# 16-PWR_2.net
KiCad netlist of a schematic drawn in Altium Designer
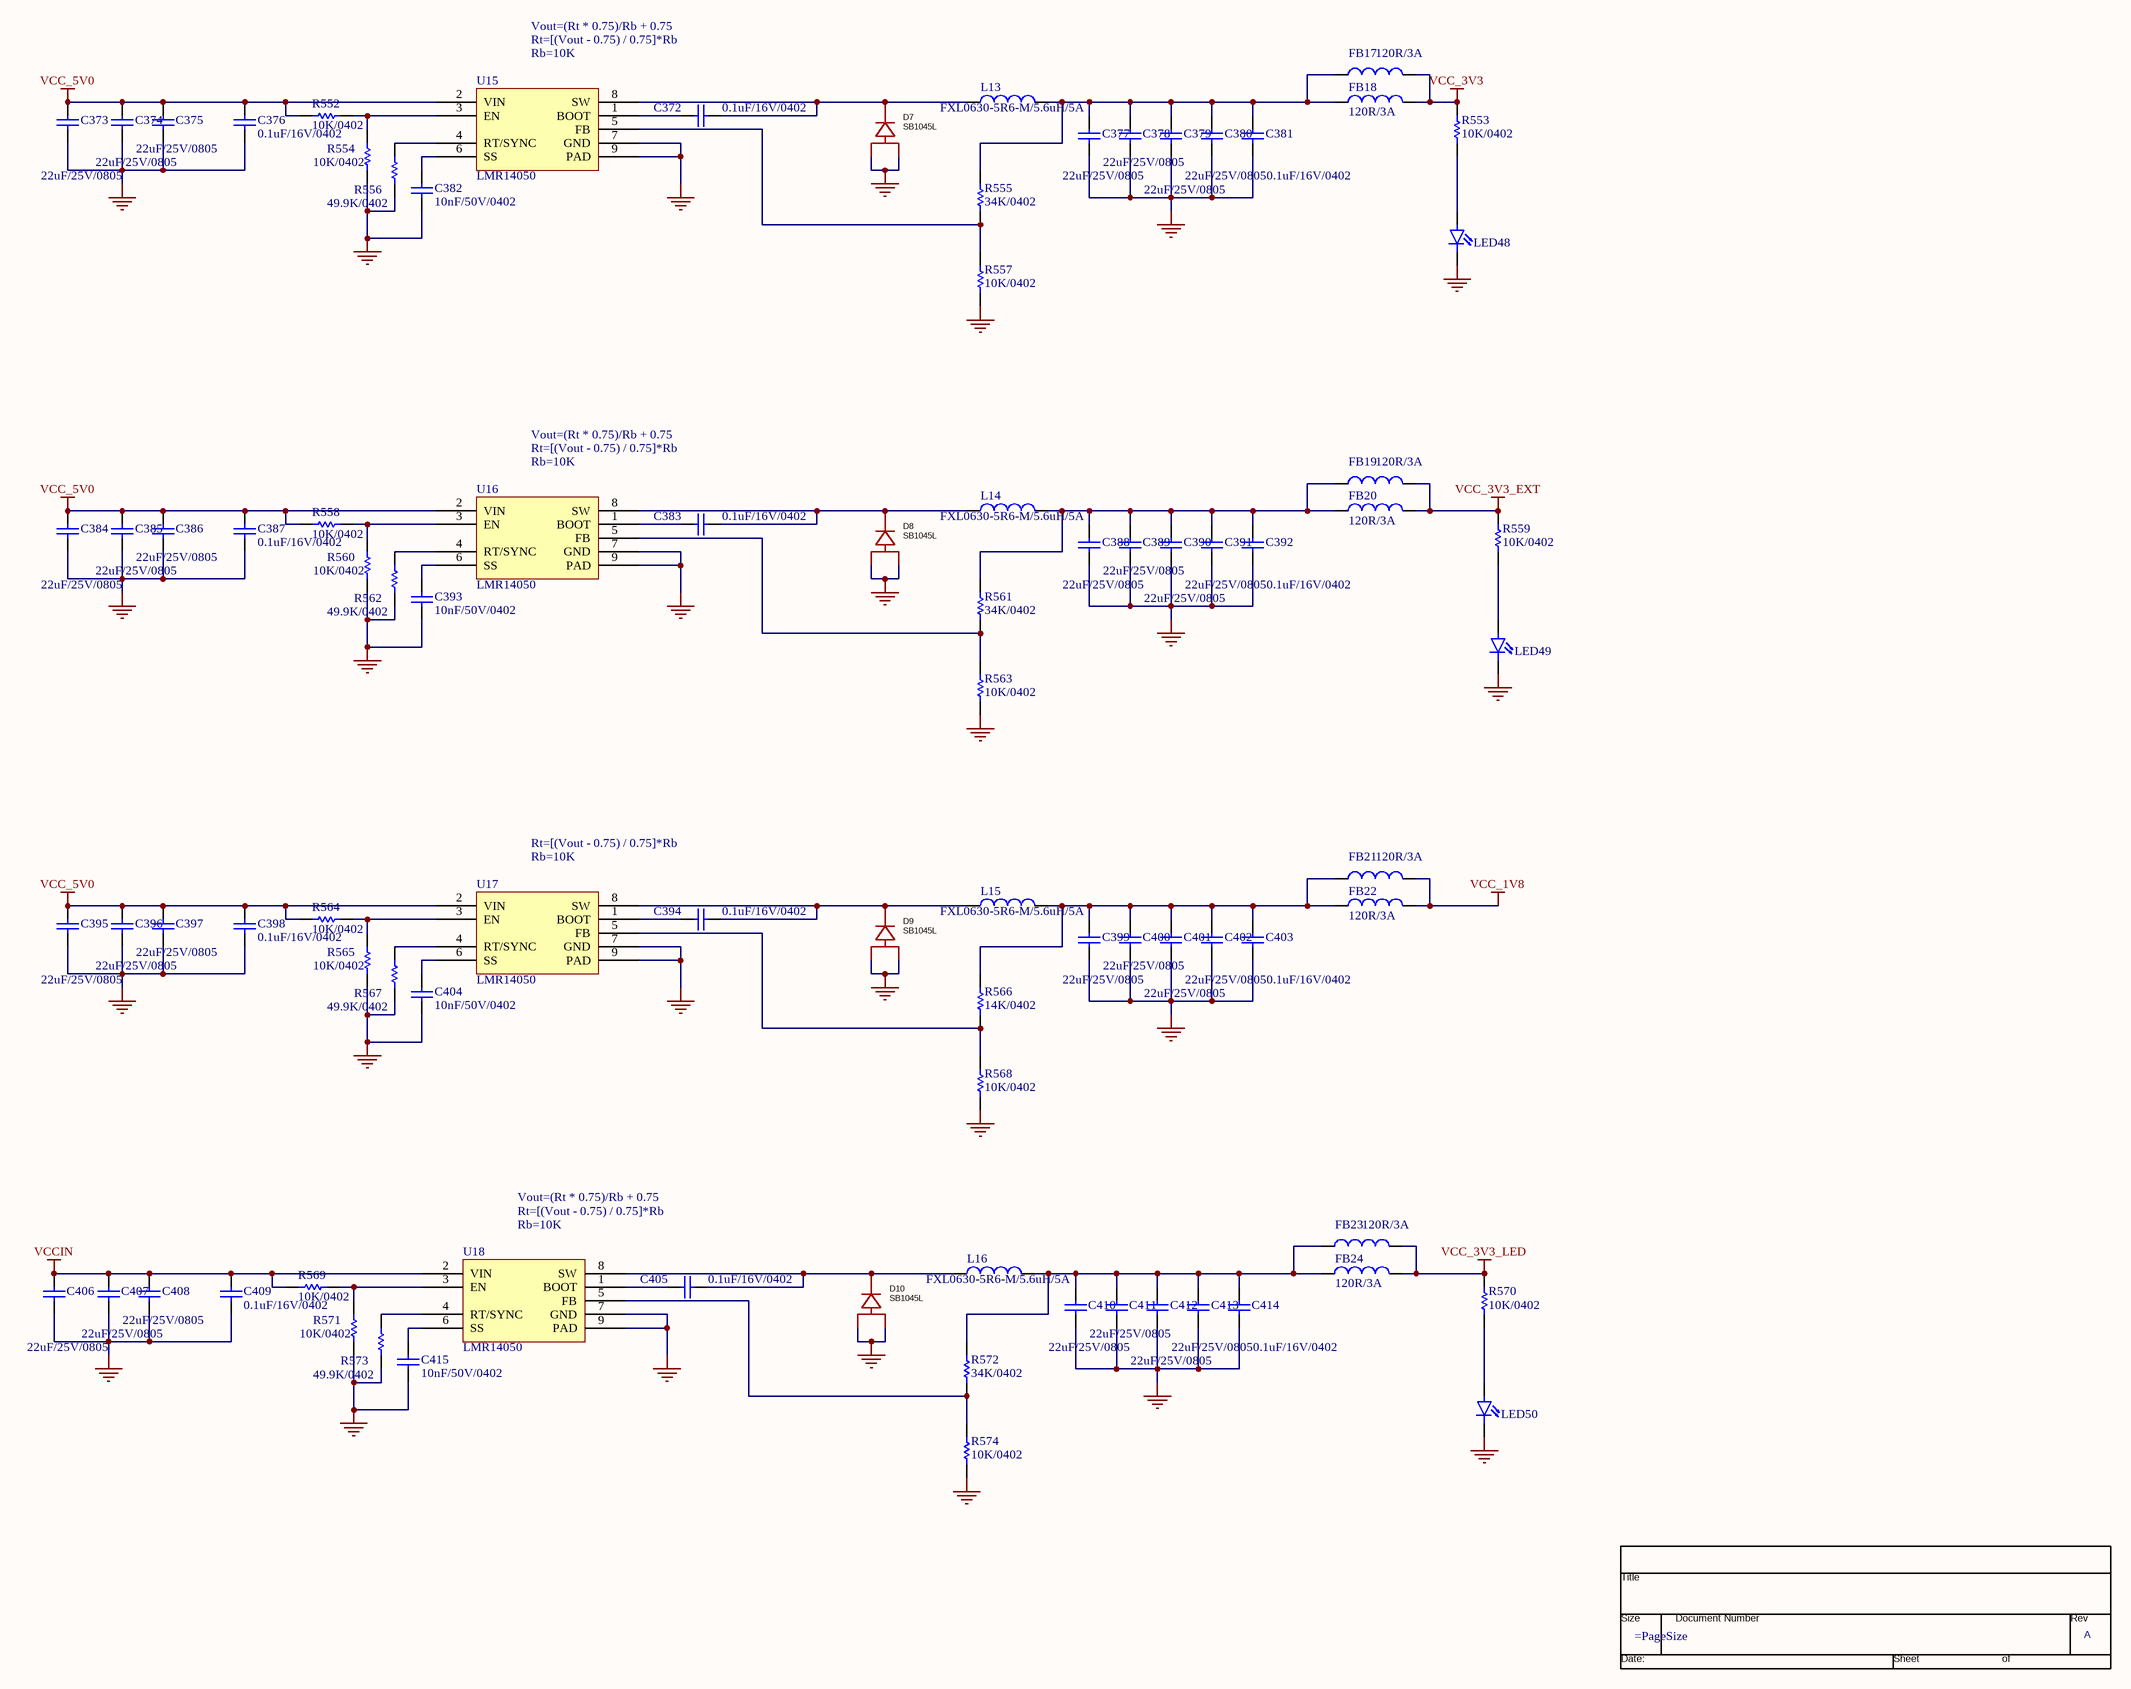
[diagram p0: 16-PWR_2.SchDoc]

(export (version "E")
  (design (tool "Eeschema 10.0.6"))
  (components
    (comp (ref "C372")
      (value "0.1uF/16V/0402")
      (description "Capacitor")
      (fields (field (name "PUBLISHER") "Altium Limited"))
      (libsource (lib "LIBS") (part "CAP"))
    )
    (comp (ref "C373")
      (value "22uF/25V/0805")
      (description "Capacitor")
      (fields (field (name "PUBLISHER") "Altium Limited"))
      (libsource (lib "LIBS") (part "CAP"))
    )
    (comp (ref "C374")
      (value "22uF/25V/0805")
      (description "Capacitor")
      (fields (field (name "PUBLISHER") "Altium Limited"))
      (libsource (lib "LIBS") (part "CAP"))
    )
    (comp (ref "C375")
      (value "22uF/25V/0805")
      (description "Capacitor")
      (fields (field (name "PUBLISHER") "Altium Limited"))
      (libsource (lib "LIBS") (part "CAP"))
    )
    (comp (ref "C376")
      (value "0.1uF/16V/0402")
      (description "Capacitor")
      (fields (field (name "PUBLISHER") "Altium Limited"))
      (libsource (lib "LIBS") (part "CAP"))
    )
    (comp (ref "C377")
      (value "22uF/25V/0805")
      (description "Capacitor")
      (fields (field (name "PUBLISHER") "Altium Limited"))
      (libsource (lib "LIBS") (part "CAP"))
    )
    (comp (ref "C378")
      (value "22uF/25V/0805")
      (description "Capacitor")
      (fields (field (name "PUBLISHER") "Altium Limited"))
      (libsource (lib "LIBS") (part "CAP"))
    )
    (comp (ref "C379")
      (value "22uF/25V/0805")
      (description "Capacitor")
      (fields (field (name "PUBLISHER") "Altium Limited"))
      (libsource (lib "LIBS") (part "CAP"))
    )
    (comp (ref "C380")
      (value "22uF/25V/0805")
      (description "Capacitor")
      (fields (field (name "PUBLISHER") "Altium Limited"))
      (libsource (lib "LIBS") (part "CAP"))
    )
    (comp (ref "C381")
      (value "0.1uF/16V/0402")
      (description "Capacitor")
      (fields (field (name "PUBLISHER") "Altium Limited"))
      (libsource (lib "LIBS") (part "CAP"))
    )
    (comp (ref "C382")
      (value "10nF/50V/0402")
      (description "Capacitor")
      (fields (field (name "PUBLISHER") "Altium Limited"))
      (libsource (lib "LIBS") (part "CAP"))
    )
    (comp (ref "C383")
      (value "0.1uF/16V/0402")
      (description "Capacitor")
      (fields (field (name "PUBLISHER") "Altium Limited"))
      (libsource (lib "LIBS") (part "CAP"))
    )
    (comp (ref "C384")
      (value "22uF/25V/0805")
      (description "Capacitor")
      (fields (field (name "PUBLISHER") "Altium Limited"))
      (libsource (lib "LIBS") (part "CAP"))
    )
    (comp (ref "C385")
      (value "22uF/25V/0805")
      (description "Capacitor")
      (fields (field (name "PUBLISHER") "Altium Limited"))
      (libsource (lib "LIBS") (part "CAP"))
    )
    (comp (ref "C386")
      (value "22uF/25V/0805")
      (description "Capacitor")
      (fields (field (name "PUBLISHER") "Altium Limited"))
      (libsource (lib "LIBS") (part "CAP"))
    )
    (comp (ref "C387")
      (value "0.1uF/16V/0402")
      (description "Capacitor")
      (fields (field (name "PUBLISHER") "Altium Limited"))
      (libsource (lib "LIBS") (part "CAP"))
    )
    (comp (ref "C388")
      (value "22uF/25V/0805")
      (description "Capacitor")
      (fields (field (name "PUBLISHER") "Altium Limited"))
      (libsource (lib "LIBS") (part "CAP"))
    )
    (comp (ref "C389")
      (value "22uF/25V/0805")
      (description "Capacitor")
      (fields (field (name "PUBLISHER") "Altium Limited"))
      (libsource (lib "LIBS") (part "CAP"))
    )
    (comp (ref "C390")
      (value "22uF/25V/0805")
      (description "Capacitor")
      (fields (field (name "PUBLISHER") "Altium Limited"))
      (libsource (lib "LIBS") (part "CAP"))
    )
    (comp (ref "C391")
      (value "22uF/25V/0805")
      (description "Capacitor")
      (fields (field (name "PUBLISHER") "Altium Limited"))
      (libsource (lib "LIBS") (part "CAP"))
    )
    (comp (ref "C392")
      (value "0.1uF/16V/0402")
      (description "Capacitor")
      (fields (field (name "PUBLISHER") "Altium Limited"))
      (libsource (lib "LIBS") (part "CAP"))
    )
    (comp (ref "C393")
      (value "10nF/50V/0402")
      (description "Capacitor")
      (fields (field (name "PUBLISHER") "Altium Limited"))
      (libsource (lib "LIBS") (part "CAP"))
    )
    (comp (ref "C394")
      (value "0.1uF/16V/0402")
      (description "Capacitor")
      (fields (field (name "PUBLISHER") "Altium Limited"))
      (libsource (lib "LIBS") (part "CAP"))
    )
    (comp (ref "C395")
      (value "22uF/25V/0805")
      (description "Capacitor")
      (fields (field (name "PUBLISHER") "Altium Limited"))
      (libsource (lib "LIBS") (part "CAP"))
    )
    (comp (ref "C396")
      (value "22uF/25V/0805")
      (description "Capacitor")
      (fields (field (name "PUBLISHER") "Altium Limited"))
      (libsource (lib "LIBS") (part "CAP"))
    )
    (comp (ref "C397")
      (value "22uF/25V/0805")
      (description "Capacitor")
      (fields (field (name "PUBLISHER") "Altium Limited"))
      (libsource (lib "LIBS") (part "CAP"))
    )
    (comp (ref "C398")
      (value "0.1uF/16V/0402")
      (description "Capacitor")
      (fields (field (name "PUBLISHER") "Altium Limited"))
      (libsource (lib "LIBS") (part "CAP"))
    )
    (comp (ref "C399")
      (value "22uF/25V/0805")
      (description "Capacitor")
      (fields (field (name "PUBLISHER") "Altium Limited"))
      (libsource (lib "LIBS") (part "CAP"))
    )
    (comp (ref "C400")
      (value "22uF/25V/0805")
      (description "Capacitor")
      (fields (field (name "PUBLISHER") "Altium Limited"))
      (libsource (lib "LIBS") (part "CAP"))
    )
    (comp (ref "C401")
      (value "22uF/25V/0805")
      (description "Capacitor")
      (fields (field (name "PUBLISHER") "Altium Limited"))
      (libsource (lib "LIBS") (part "CAP"))
    )
    (comp (ref "C402")
      (value "22uF/25V/0805")
      (description "Capacitor")
      (fields (field (name "PUBLISHER") "Altium Limited"))
      (libsource (lib "LIBS") (part "CAP"))
    )
    (comp (ref "C403")
      (value "0.1uF/16V/0402")
      (description "Capacitor")
      (fields (field (name "PUBLISHER") "Altium Limited"))
      (libsource (lib "LIBS") (part "CAP"))
    )
    (comp (ref "C404")
      (value "10nF/50V/0402")
      (description "Capacitor")
      (fields (field (name "PUBLISHER") "Altium Limited"))
      (libsource (lib "LIBS") (part "CAP"))
    )
    (comp (ref "C405")
      (value "0.1uF/16V/0402")
      (description "Capacitor")
      (fields (field (name "PUBLISHER") "Altium Limited"))
      (libsource (lib "LIBS") (part "CAP"))
    )
    (comp (ref "C406")
      (value "22uF/25V/0805")
      (description "Capacitor")
      (fields (field (name "PUBLISHER") "Altium Limited"))
      (libsource (lib "LIBS") (part "CAP"))
    )
    (comp (ref "C407")
      (value "22uF/25V/0805")
      (description "Capacitor")
      (fields (field (name "PUBLISHER") "Altium Limited"))
      (libsource (lib "LIBS") (part "CAP"))
    )
    (comp (ref "C408")
      (value "22uF/25V/0805")
      (description "Capacitor")
      (fields (field (name "PUBLISHER") "Altium Limited"))
      (libsource (lib "LIBS") (part "CAP"))
    )
    (comp (ref "C409")
      (value "0.1uF/16V/0402")
      (description "Capacitor")
      (fields (field (name "PUBLISHER") "Altium Limited"))
      (libsource (lib "LIBS") (part "CAP"))
    )
    (comp (ref "C410")
      (value "22uF/25V/0805")
      (description "Capacitor")
      (fields (field (name "PUBLISHER") "Altium Limited"))
      (libsource (lib "LIBS") (part "CAP"))
    )
    (comp (ref "C411")
      (value "22uF/25V/0805")
      (description "Capacitor")
      (fields (field (name "PUBLISHER") "Altium Limited"))
      (libsource (lib "LIBS") (part "CAP"))
    )
    (comp (ref "C412")
      (value "22uF/25V/0805")
      (description "Capacitor")
      (fields (field (name "PUBLISHER") "Altium Limited"))
      (libsource (lib "LIBS") (part "CAP"))
    )
    (comp (ref "C413")
      (value "22uF/25V/0805")
      (description "Capacitor")
      (fields (field (name "PUBLISHER") "Altium Limited"))
      (libsource (lib "LIBS") (part "CAP"))
    )
    (comp (ref "C414")
      (value "0.1uF/16V/0402")
      (description "Capacitor")
      (fields (field (name "PUBLISHER") "Altium Limited"))
      (libsource (lib "LIBS") (part "CAP"))
    )
    (comp (ref "C415")
      (value "10nF/50V/0402")
      (description "Capacitor")
      (fields (field (name "PUBLISHER") "Altium Limited"))
      (libsource (lib "LIBS") (part "CAP"))
    )
    (comp (ref "D7")
      (value "SB1045L")
      (footprint "TO-277_3P-L5.4-W4.0-LS6.5-TR")
      (fields (field (name "MANUFACTURER") "GOODWORK(固得沃克)"))
      (libsource (lib "altium-import") (part "root_3_SB1045L_C908747_"))
    )
    (comp (ref "D8")
      (value "SB1045L")
      (footprint "TO-277_3P-L5.4-W4.0-LS6.5-TR")
      (fields (field (name "MANUFACTURER") "GOODWORK(固得沃克)"))
      (libsource (lib "altium-import") (part "root_3_SB1045L_C908747_"))
    )
    (comp (ref "D9")
      (value "SB1045L")
      (footprint "TO-277_3P-L5.4-W4.0-LS6.5-TR")
      (fields (field (name "MANUFACTURER") "GOODWORK(固得沃克)"))
      (libsource (lib "altium-import") (part "root_3_SB1045L_C908747_"))
    )
    (comp (ref "D10")
      (value "SB1045L")
      (footprint "TO-277_3P-L5.4-W4.0-LS6.5-TR")
      (fields (field (name "MANUFACTURER") "GOODWORK(固得沃克)"))
      (libsource (lib "altium-import") (part "root_3_SB1045L_C908747_"))
    )
    (comp (ref "FB17")
      (value "120R/3A")
      (footprint "L0603")
      (description "BLM18KG121TN1D")
      (fields (field (name "PUBLISHER") "Altium Limited"))
      (libsource (lib "LIBS") (part "Inductor"))
    )
    (comp (ref "FB18")
      (value "120R/3A")
      (footprint "L0603")
      (description "BLM18KG121TN1D")
      (fields (field (name "PUBLISHER") "Altium Limited"))
      (libsource (lib "LIBS") (part "Inductor"))
    )
    (comp (ref "FB19")
      (value "120R/3A")
      (footprint "L0603")
      (description "BLM18KG121TN1D")
      (fields (field (name "PUBLISHER") "Altium Limited"))
      (libsource (lib "LIBS") (part "Inductor"))
    )
    (comp (ref "FB20")
      (value "120R/3A")
      (footprint "L0603")
      (description "BLM18KG121TN1D")
      (fields (field (name "PUBLISHER") "Altium Limited"))
      (libsource (lib "LIBS") (part "Inductor"))
    )
    (comp (ref "FB21")
      (value "120R/3A")
      (footprint "L0603")
      (description "BLM18KG121TN1D")
      (fields (field (name "PUBLISHER") "Altium Limited"))
      (libsource (lib "LIBS") (part "Inductor"))
    )
    (comp (ref "FB22")
      (value "120R/3A")
      (footprint "L0603")
      (description "BLM18KG121TN1D")
      (fields (field (name "PUBLISHER") "Altium Limited"))
      (libsource (lib "LIBS") (part "Inductor"))
    )
    (comp (ref "FB23")
      (value "120R/3A")
      (footprint "L0603")
      (description "BLM18KG121TN1D")
      (fields (field (name "PUBLISHER") "Altium Limited"))
      (libsource (lib "LIBS") (part "Inductor"))
    )
    (comp (ref "FB24")
      (value "120R/3A")
      (footprint "L0603")
      (description "BLM18KG121TN1D")
      (fields (field (name "PUBLISHER") "Altium Limited"))
      (libsource (lib "LIBS") (part "Inductor"))
    )
    (comp (ref "L13")
      (value "FXL0630-5R6-M/5.6uH/5A")
      (footprint "FXL0630-5R6-M")
      (description "FXC0630-5R6M")
      (fields (field (name "PUBLISHER") "Altium Limited"))
      (libsource (lib "LIBS") (part "Inductor"))
    )
    (comp (ref "L14")
      (value "FXL0630-5R6-M/5.6uH/5A")
      (footprint "FXL0630-5R6-M")
      (description "FXC0630-5R6M")
      (fields (field (name "PUBLISHER") "Altium Limited"))
      (libsource (lib "LIBS") (part "Inductor"))
    )
    (comp (ref "L15")
      (value "FXL0630-5R6-M/5.6uH/5A")
      (footprint "FXL0630-5R6-M")
      (description "FXC0630-5R6M")
      (fields (field (name "PUBLISHER") "Altium Limited"))
      (libsource (lib "LIBS") (part "Inductor"))
    )
    (comp (ref "L16")
      (value "FXL0630-5R6-M/5.6uH/5A")
      (footprint "FXL0630-5R6-M")
      (description "FXC0630-5R6M")
      (fields (field (name "PUBLISHER") "Altium Limited"))
      (libsource (lib "LIBS") (part "Inductor"))
    )
    (comp (ref "LED48") (value "LED_GREEN") (footprint "LED0603") (libsource (lib "LIBS") (part "LED")))
    (comp (ref "LED49") (value "LED_GREEN") (footprint "LED0603") (libsource (lib "LIBS") (part "LED")))
    (comp (ref "LED50") (value "LED_GREEN") (footprint "LED0603") (libsource (lib "LIBS") (part "LED")))
    (comp (ref "R552")
      (value "10K/0402")
      (footprint "R0402")
      (description "Semiconductor Resistor")
      (fields (field (name "PUBLISHER") "Altium Limited"))
      (libsource (lib "LIBS") (part "Res Semi"))
    )
    (comp (ref "R553")
      (value "10K/0402")
      (footprint "R0402")
      (description "Semiconductor Resistor")
      (fields (field (name "PUBLISHER") "Altium Limited"))
      (libsource (lib "LIBS") (part "Res Semi"))
    )
    (comp (ref "R554")
      (value "10K/0402")
      (footprint "R0402")
      (description "Semiconductor Resistor")
      (fields (field (name "PUBLISHER") "Altium Limited"))
      (libsource (lib "LIBS") (part "Res Semi"))
    )
    (comp (ref "R555")
      (value "34K/0402")
      (footprint "R0402")
      (description "Semiconductor Resistor")
      (fields (field (name "PUBLISHER") "Altium Limited"))
      (libsource (lib "LIBS") (part "Res Semi"))
    )
    (comp (ref "R556")
      (value "49.9K/0402")
      (footprint "R0402")
      (description "Semiconductor Resistor")
      (fields (field (name "PUBLISHER") "Altium Limited"))
      (libsource (lib "LIBS") (part "Res Semi"))
    )
    (comp (ref "R557")
      (value "10K/0402")
      (footprint "R0402")
      (description "Semiconductor Resistor")
      (fields (field (name "PUBLISHER") "Altium Limited"))
      (libsource (lib "LIBS") (part "Res Semi"))
    )
    (comp (ref "R558")
      (value "10K/0402")
      (footprint "R0402")
      (description "Semiconductor Resistor")
      (fields (field (name "PUBLISHER") "Altium Limited"))
      (libsource (lib "LIBS") (part "Res Semi"))
    )
    (comp (ref "R559")
      (value "10K/0402")
      (footprint "R0402")
      (description "Semiconductor Resistor")
      (fields (field (name "PUBLISHER") "Altium Limited"))
      (libsource (lib "LIBS") (part "Res Semi"))
    )
    (comp (ref "R560")
      (value "10K/0402")
      (footprint "R0402")
      (description "Semiconductor Resistor")
      (fields (field (name "PUBLISHER") "Altium Limited"))
      (libsource (lib "LIBS") (part "Res Semi"))
    )
    (comp (ref "R561")
      (value "34K/0402")
      (footprint "R0402")
      (description "Semiconductor Resistor")
      (fields (field (name "PUBLISHER") "Altium Limited"))
      (libsource (lib "LIBS") (part "Res Semi"))
    )
    (comp (ref "R562")
      (value "49.9K/0402")
      (footprint "R0402")
      (description "Semiconductor Resistor")
      (fields (field (name "PUBLISHER") "Altium Limited"))
      (libsource (lib "LIBS") (part "Res Semi"))
    )
    (comp (ref "R563")
      (value "10K/0402")
      (footprint "R0402")
      (description "Semiconductor Resistor")
      (fields (field (name "PUBLISHER") "Altium Limited"))
      (libsource (lib "LIBS") (part "Res Semi"))
    )
    (comp (ref "R564")
      (value "10K/0402")
      (footprint "R0402")
      (description "Semiconductor Resistor")
      (fields (field (name "PUBLISHER") "Altium Limited"))
      (libsource (lib "LIBS") (part "Res Semi"))
    )
    (comp (ref "R565")
      (value "10K/0402")
      (footprint "R0402")
      (description "Semiconductor Resistor")
      (fields (field (name "PUBLISHER") "Altium Limited"))
      (libsource (lib "LIBS") (part "Res Semi"))
    )
    (comp (ref "R566")
      (value "14K/0402")
      (footprint "R0402")
      (description "Semiconductor Resistor")
      (fields (field (name "PUBLISHER") "Altium Limited"))
      (libsource (lib "LIBS") (part "Res Semi"))
    )
    (comp (ref "R567")
      (value "49.9K/0402")
      (footprint "R0402")
      (description "Semiconductor Resistor")
      (fields (field (name "PUBLISHER") "Altium Limited"))
      (libsource (lib "LIBS") (part "Res Semi"))
    )
    (comp (ref "R568")
      (value "10K/0402")
      (footprint "R0402")
      (description "Semiconductor Resistor")
      (fields (field (name "PUBLISHER") "Altium Limited"))
      (libsource (lib "LIBS") (part "Res Semi"))
    )
    (comp (ref "R569")
      (value "10K/0402")
      (footprint "R0402")
      (description "Semiconductor Resistor")
      (fields (field (name "PUBLISHER") "Altium Limited"))
      (libsource (lib "LIBS") (part "Res Semi"))
    )
    (comp (ref "R570")
      (value "10K/0402")
      (footprint "R0402")
      (description "Semiconductor Resistor")
      (fields (field (name "PUBLISHER") "Altium Limited"))
      (libsource (lib "LIBS") (part "Res Semi"))
    )
    (comp (ref "R571")
      (value "10K/0402")
      (footprint "R0402")
      (description "Semiconductor Resistor")
      (fields (field (name "PUBLISHER") "Altium Limited"))
      (libsource (lib "LIBS") (part "Res Semi"))
    )
    (comp (ref "R572")
      (value "34K/0402")
      (footprint "R0402")
      (description "Semiconductor Resistor")
      (fields (field (name "PUBLISHER") "Altium Limited"))
      (libsource (lib "LIBS") (part "Res Semi"))
    )
    (comp (ref "R573")
      (value "49.9K/0402")
      (footprint "R0402")
      (description "Semiconductor Resistor")
      (fields (field (name "PUBLISHER") "Altium Limited"))
      (libsource (lib "LIBS") (part "Res Semi"))
    )
    (comp (ref "R574")
      (value "10K/0402")
      (footprint "R0402")
      (description "Semiconductor Resistor")
      (fields (field (name "PUBLISHER") "Altium Limited"))
      (libsource (lib "LIBS") (part "Res Semi"))
    )
    (comp (ref "U15") (value "LMR14050") (footprint "LMR14030") (libsource (lib "LIBS") (part "LMR14030")))
    (comp (ref "U16") (value "LMR14050") (footprint "LMR14030") (libsource (lib "LIBS") (part "LMR14030")))
    (comp (ref "U17") (value "LMR14050") (footprint "LMR14030") (libsource (lib "LIBS") (part "LMR14030")))
    (comp (ref "U18") (value "LMR14050") (footprint "LMR14030") (libsource (lib "LIBS") (part "LMR14030")))
  )
  (nets
    (net (code "1") (name "GND") (class "Default")
      (node (ref "C373") (pin "1") (pinfunction "1_1") (pintype "passive"))
      (node (ref "C374") (pin "1") (pinfunction "1_1") (pintype "passive"))
      (node (ref "C375") (pin "1") (pinfunction "1_1") (pintype "passive"))
      (node (ref "C376") (pin "1") (pinfunction "1_1") (pintype "passive"))
      (node (ref "C377") (pin "1") (pinfunction "1_1") (pintype "passive"))
      (node (ref "C378") (pin "1") (pinfunction "1_1") (pintype "passive"))
      (node (ref "C379") (pin "1") (pinfunction "1_1") (pintype "passive"))
      (node (ref "C380") (pin "1") (pinfunction "1_1") (pintype "passive"))
      (node (ref "C381") (pin "1") (pinfunction "1_1") (pintype "passive"))
      (node (ref "C382") (pin "1") (pinfunction "1_1") (pintype "passive"))
      (node (ref "C384") (pin "1") (pinfunction "1_1") (pintype "passive"))
      (node (ref "C385") (pin "1") (pinfunction "1_1") (pintype "passive"))
      (node (ref "C386") (pin "1") (pinfunction "1_1") (pintype "passive"))
      (node (ref "C387") (pin "1") (pinfunction "1_1") (pintype "passive"))
      (node (ref "C388") (pin "1") (pinfunction "1_1") (pintype "passive"))
      (node (ref "C389") (pin "1") (pinfunction "1_1") (pintype "passive"))
      (node (ref "C390") (pin "1") (pinfunction "1_1") (pintype "passive"))
      (node (ref "C391") (pin "1") (pinfunction "1_1") (pintype "passive"))
      (node (ref "C392") (pin "1") (pinfunction "1_1") (pintype "passive"))
      (node (ref "C393") (pin "1") (pinfunction "1_1") (pintype "passive"))
      (node (ref "C395") (pin "1") (pinfunction "1_1") (pintype "passive"))
      (node (ref "C396") (pin "1") (pinfunction "1_1") (pintype "passive"))
      (node (ref "C397") (pin "1") (pinfunction "1_1") (pintype "passive"))
      (node (ref "C398") (pin "1") (pinfunction "1_1") (pintype "passive"))
      (node (ref "C399") (pin "1") (pinfunction "1_1") (pintype "passive"))
      (node (ref "C400") (pin "1") (pinfunction "1_1") (pintype "passive"))
      (node (ref "C401") (pin "1") (pinfunction "1_1") (pintype "passive"))
      (node (ref "C402") (pin "1") (pinfunction "1_1") (pintype "passive"))
      (node (ref "C403") (pin "1") (pinfunction "1_1") (pintype "passive"))
      (node (ref "C404") (pin "1") (pinfunction "1_1") (pintype "passive"))
      (node (ref "C406") (pin "1") (pinfunction "1_1") (pintype "passive"))
      (node (ref "C407") (pin "1") (pinfunction "1_1") (pintype "passive"))
      (node (ref "C408") (pin "1") (pinfunction "1_1") (pintype "passive"))
      (node (ref "C409") (pin "1") (pinfunction "1_1") (pintype "passive"))
      (node (ref "C410") (pin "1") (pinfunction "1_1") (pintype "passive"))
      (node (ref "C411") (pin "1") (pinfunction "1_1") (pintype "passive"))
      (node (ref "C412") (pin "1") (pinfunction "1_1") (pintype "passive"))
      (node (ref "C413") (pin "1") (pinfunction "1_1") (pintype "passive"))
      (node (ref "C414") (pin "1") (pinfunction "1_1") (pintype "passive"))
      (node (ref "C415") (pin "1") (pinfunction "1_1") (pintype "passive"))
      (node (ref "D10") (pin "1") (pinfunction "A_1") (pintype "passive"))
      (node (ref "D10") (pin "3") (pinfunction "A_3") (pintype "passive"))
      (node (ref "D7") (pin "1") (pinfunction "A_1") (pintype "passive"))
      (node (ref "D7") (pin "3") (pinfunction "A_3") (pintype "passive"))
      (node (ref "D8") (pin "1") (pinfunction "A_1") (pintype "passive"))
      (node (ref "D8") (pin "3") (pinfunction "A_3") (pintype "passive"))
      (node (ref "D9") (pin "1") (pinfunction "A_1") (pintype "passive"))
      (node (ref "D9") (pin "3") (pinfunction "A_3") (pintype "passive"))
      (node (ref "LED48") (pin "2") (pinfunction "2_2") (pintype "passive"))
      (node (ref "LED49") (pin "2") (pinfunction "2_2") (pintype "passive"))
      (node (ref "LED50") (pin "2") (pinfunction "2_2") (pintype "passive"))
      (node (ref "R554") (pin "2") (pinfunction "2_2") (pintype "passive"))
      (node (ref "R556") (pin "2") (pinfunction "2_2") (pintype "passive"))
      (node (ref "R557") (pin "2") (pinfunction "2_2") (pintype "passive"))
      (node (ref "R560") (pin "2") (pinfunction "2_2") (pintype "passive"))
      (node (ref "R562") (pin "2") (pinfunction "2_2") (pintype "passive"))
      (node (ref "R563") (pin "2") (pinfunction "2_2") (pintype "passive"))
      (node (ref "R565") (pin "2") (pinfunction "2_2") (pintype "passive"))
      (node (ref "R567") (pin "2") (pinfunction "2_2") (pintype "passive"))
      (node (ref "R568") (pin "2") (pinfunction "2_2") (pintype "passive"))
      (node (ref "R571") (pin "2") (pinfunction "2_2") (pintype "passive"))
      (node (ref "R573") (pin "2") (pinfunction "2_2") (pintype "passive"))
      (node (ref "R574") (pin "2") (pinfunction "2_2") (pintype "passive"))
      (node (ref "U15") (pin "7") (pinfunction "GND_7") (pintype "passive"))
      (node (ref "U15") (pin "9") (pinfunction "PAD_9") (pintype "passive"))
      (node (ref "U16") (pin "7") (pinfunction "GND_7") (pintype "passive"))
      (node (ref "U16") (pin "9") (pinfunction "PAD_9") (pintype "passive"))
      (node (ref "U17") (pin "7") (pinfunction "GND_7") (pintype "passive"))
      (node (ref "U17") (pin "9") (pinfunction "PAD_9") (pintype "passive"))
      (node (ref "U18") (pin "7") (pinfunction "GND_7") (pintype "passive"))
      (node (ref "U18") (pin "9") (pinfunction "PAD_9") (pintype "passive"))
    )
    (net (code "2") (name "Net-(C377-Pad2)") (class "Default")
      (node (ref "C377") (pin "2") (pinfunction "2_2") (pintype "passive"))
      (node (ref "C378") (pin "2") (pinfunction "2_2") (pintype "passive"))
      (node (ref "C379") (pin "2") (pinfunction "2_2") (pintype "passive"))
      (node (ref "C380") (pin "2") (pinfunction "2_2") (pintype "passive"))
      (node (ref "C381") (pin "2") (pinfunction "2_2") (pintype "passive"))
      (node (ref "FB17") (pin "1") (pinfunction "1_1") (pintype "passive"))
      (node (ref "FB18") (pin "1") (pinfunction "1_1") (pintype "passive"))
      (node (ref "L13") (pin "2") (pinfunction "2_2") (pintype "passive"))
      (node (ref "R555") (pin "1") (pinfunction "1_1") (pintype "passive"))
    )
    (net (code "3") (name "Net-(C388-Pad2)") (class "Default")
      (node (ref "C388") (pin "2") (pinfunction "2_2") (pintype "passive"))
      (node (ref "C389") (pin "2") (pinfunction "2_2") (pintype "passive"))
      (node (ref "C390") (pin "2") (pinfunction "2_2") (pintype "passive"))
      (node (ref "C391") (pin "2") (pinfunction "2_2") (pintype "passive"))
      (node (ref "C392") (pin "2") (pinfunction "2_2") (pintype "passive"))
      (node (ref "FB19") (pin "1") (pinfunction "1_1") (pintype "passive"))
      (node (ref "FB20") (pin "1") (pinfunction "1_1") (pintype "passive"))
      (node (ref "L14") (pin "2") (pinfunction "2_2") (pintype "passive"))
      (node (ref "R561") (pin "1") (pinfunction "1_1") (pintype "passive"))
    )
    (net (code "4") (name "Net-(C399-Pad2)") (class "Default")
      (node (ref "C399") (pin "2") (pinfunction "2_2") (pintype "passive"))
      (node (ref "C400") (pin "2") (pinfunction "2_2") (pintype "passive"))
      (node (ref "C401") (pin "2") (pinfunction "2_2") (pintype "passive"))
      (node (ref "C402") (pin "2") (pinfunction "2_2") (pintype "passive"))
      (node (ref "C403") (pin "2") (pinfunction "2_2") (pintype "passive"))
      (node (ref "FB21") (pin "1") (pinfunction "1_1") (pintype "passive"))
      (node (ref "FB22") (pin "1") (pinfunction "1_1") (pintype "passive"))
      (node (ref "L15") (pin "2") (pinfunction "2_2") (pintype "passive"))
      (node (ref "R566") (pin "1") (pinfunction "1_1") (pintype "passive"))
    )
    (net (code "5") (name "Net-(C410-Pad2)") (class "Default")
      (node (ref "C410") (pin "2") (pinfunction "2_2") (pintype "passive"))
      (node (ref "C411") (pin "2") (pinfunction "2_2") (pintype "passive"))
      (node (ref "C412") (pin "2") (pinfunction "2_2") (pintype "passive"))
      (node (ref "C413") (pin "2") (pinfunction "2_2") (pintype "passive"))
      (node (ref "C414") (pin "2") (pinfunction "2_2") (pintype "passive"))
      (node (ref "FB23") (pin "1") (pinfunction "1_1") (pintype "passive"))
      (node (ref "FB24") (pin "1") (pinfunction "1_1") (pintype "passive"))
      (node (ref "L16") (pin "2") (pinfunction "2_2") (pintype "passive"))
      (node (ref "R572") (pin "1") (pinfunction "1_1") (pintype "passive"))
    )
    (net (code "6") (name "Net-(D7-K)") (class "Default")
      (node (ref "C372") (pin "1") (pinfunction "1_1") (pintype "passive"))
      (node (ref "D7") (pin "2") (pinfunction "K_2") (pintype "passive"))
      (node (ref "L13") (pin "1") (pinfunction "1_1") (pintype "passive"))
      (node (ref "U15") (pin "8") (pinfunction "SW_8") (pintype "passive"))
    )
    (net (code "7") (name "Net-(D8-K)") (class "Default")
      (node (ref "C383") (pin "1") (pinfunction "1_1") (pintype "passive"))
      (node (ref "D8") (pin "2") (pinfunction "K_2") (pintype "passive"))
      (node (ref "L14") (pin "1") (pinfunction "1_1") (pintype "passive"))
      (node (ref "U16") (pin "8") (pinfunction "SW_8") (pintype "passive"))
    )
    (net (code "8") (name "Net-(D9-K)") (class "Default")
      (node (ref "C394") (pin "1") (pinfunction "1_1") (pintype "passive"))
      (node (ref "D9") (pin "2") (pinfunction "K_2") (pintype "passive"))
      (node (ref "L15") (pin "1") (pinfunction "1_1") (pintype "passive"))
      (node (ref "U17") (pin "8") (pinfunction "SW_8") (pintype "passive"))
    )
    (net (code "9") (name "Net-(D10-K)") (class "Default")
      (node (ref "C405") (pin "1") (pinfunction "1_1") (pintype "passive"))
      (node (ref "D10") (pin "2") (pinfunction "K_2") (pintype "passive"))
      (node (ref "L16") (pin "1") (pinfunction "1_1") (pintype "passive"))
      (node (ref "U18") (pin "8") (pinfunction "SW_8") (pintype "passive"))
    )
    (net (code "10") (name "Net-(LED48-Pad1)") (class "Default")
      (node (ref "LED48") (pin "1") (pinfunction "1_1") (pintype "passive"))
      (node (ref "R553") (pin "2") (pinfunction "2_2") (pintype "passive"))
    )
    (net (code "11") (name "Net-(LED49-Pad1)") (class "Default")
      (node (ref "LED49") (pin "1") (pinfunction "1_1") (pintype "passive"))
      (node (ref "R559") (pin "2") (pinfunction "2_2") (pintype "passive"))
    )
    (net (code "12") (name "Net-(LED50-Pad1)") (class "Default")
      (node (ref "LED50") (pin "1") (pinfunction "1_1") (pintype "passive"))
      (node (ref "R570") (pin "2") (pinfunction "2_2") (pintype "passive"))
    )
    (net (code "13") (name "Net-(U15-BOOT)") (class "Default")
      (node (ref "C372") (pin "2") (pinfunction "2_2") (pintype "passive"))
      (node (ref "U15") (pin "1") (pinfunction "BOOT_1") (pintype "passive"))
    )
    (net (code "14") (name "Net-(U15-EN)") (class "Default")
      (node (ref "R552") (pin "1") (pinfunction "1_1") (pintype "passive"))
      (node (ref "R554") (pin "1") (pinfunction "1_1") (pintype "passive"))
      (node (ref "U15") (pin "3") (pinfunction "EN_3") (pintype "passive"))
    )
    (net (code "15") (name "Net-(U15-FB)") (class "Default")
      (node (ref "R555") (pin "2") (pinfunction "2_2") (pintype "passive"))
      (node (ref "R557") (pin "1") (pinfunction "1_1") (pintype "passive"))
      (node (ref "U15") (pin "5") (pinfunction "FB_5") (pintype "passive"))
    )
    (net (code "16") (name "Net-(U15-RT{slash}SYNC)") (class "Default")
      (node (ref "R556") (pin "1") (pinfunction "1_1") (pintype "passive"))
      (node (ref "U15") (pin "4") (pinfunction "RT/SYNC_4") (pintype "passive"))
    )
    (net (code "17") (name "Net-(U15-SS)") (class "Default")
      (node (ref "C382") (pin "2") (pinfunction "2_2") (pintype "passive"))
      (node (ref "U15") (pin "6") (pinfunction "SS_6") (pintype "passive"))
    )
    (net (code "18") (name "Net-(U16-BOOT)") (class "Default")
      (node (ref "C383") (pin "2") (pinfunction "2_2") (pintype "passive"))
      (node (ref "U16") (pin "1") (pinfunction "BOOT_1") (pintype "passive"))
    )
    (net (code "19") (name "Net-(U16-EN)") (class "Default")
      (node (ref "R558") (pin "1") (pinfunction "1_1") (pintype "passive"))
      (node (ref "R560") (pin "1") (pinfunction "1_1") (pintype "passive"))
      (node (ref "U16") (pin "3") (pinfunction "EN_3") (pintype "passive"))
    )
    (net (code "20") (name "Net-(U16-FB)") (class "Default")
      (node (ref "R561") (pin "2") (pinfunction "2_2") (pintype "passive"))
      (node (ref "R563") (pin "1") (pinfunction "1_1") (pintype "passive"))
      (node (ref "U16") (pin "5") (pinfunction "FB_5") (pintype "passive"))
    )
    (net (code "21") (name "Net-(U16-RT{slash}SYNC)") (class "Default")
      (node (ref "R562") (pin "1") (pinfunction "1_1") (pintype "passive"))
      (node (ref "U16") (pin "4") (pinfunction "RT/SYNC_4") (pintype "passive"))
    )
    (net (code "22") (name "Net-(U16-SS)") (class "Default")
      (node (ref "C393") (pin "2") (pinfunction "2_2") (pintype "passive"))
      (node (ref "U16") (pin "6") (pinfunction "SS_6") (pintype "passive"))
    )
    (net (code "23") (name "Net-(U17-BOOT)") (class "Default")
      (node (ref "C394") (pin "2") (pinfunction "2_2") (pintype "passive"))
      (node (ref "U17") (pin "1") (pinfunction "BOOT_1") (pintype "passive"))
    )
    (net (code "24") (name "Net-(U17-EN)") (class "Default")
      (node (ref "R564") (pin "1") (pinfunction "1_1") (pintype "passive"))
      (node (ref "R565") (pin "1") (pinfunction "1_1") (pintype "passive"))
      (node (ref "U17") (pin "3") (pinfunction "EN_3") (pintype "passive"))
    )
    (net (code "25") (name "Net-(U17-FB)") (class "Default")
      (node (ref "R566") (pin "2") (pinfunction "2_2") (pintype "passive"))
      (node (ref "R568") (pin "1") (pinfunction "1_1") (pintype "passive"))
      (node (ref "U17") (pin "5") (pinfunction "FB_5") (pintype "passive"))
    )
    (net (code "26") (name "Net-(U17-RT{slash}SYNC)") (class "Default")
      (node (ref "R567") (pin "1") (pinfunction "1_1") (pintype "passive"))
      (node (ref "U17") (pin "4") (pinfunction "RT/SYNC_4") (pintype "passive"))
    )
    (net (code "27") (name "Net-(U17-SS)") (class "Default")
      (node (ref "C404") (pin "2") (pinfunction "2_2") (pintype "passive"))
      (node (ref "U17") (pin "6") (pinfunction "SS_6") (pintype "passive"))
    )
    (net (code "28") (name "Net-(U18-BOOT)") (class "Default")
      (node (ref "C405") (pin "2") (pinfunction "2_2") (pintype "passive"))
      (node (ref "U18") (pin "1") (pinfunction "BOOT_1") (pintype "passive"))
    )
    (net (code "29") (name "Net-(U18-EN)") (class "Default")
      (node (ref "R569") (pin "1") (pinfunction "1_1") (pintype "passive"))
      (node (ref "R571") (pin "1") (pinfunction "1_1") (pintype "passive"))
      (node (ref "U18") (pin "3") (pinfunction "EN_3") (pintype "passive"))
    )
    (net (code "30") (name "Net-(U18-FB)") (class "Default")
      (node (ref "R572") (pin "2") (pinfunction "2_2") (pintype "passive"))
      (node (ref "R574") (pin "1") (pinfunction "1_1") (pintype "passive"))
      (node (ref "U18") (pin "5") (pinfunction "FB_5") (pintype "passive"))
    )
    (net (code "31") (name "Net-(U18-RT{slash}SYNC)") (class "Default")
      (node (ref "R573") (pin "1") (pinfunction "1_1") (pintype "passive"))
      (node (ref "U18") (pin "4") (pinfunction "RT/SYNC_4") (pintype "passive"))
    )
    (net (code "32") (name "Net-(U18-SS)") (class "Default")
      (node (ref "C415") (pin "2") (pinfunction "2_2") (pintype "passive"))
      (node (ref "U18") (pin "6") (pinfunction "SS_6") (pintype "passive"))
    )
    (net (code "33") (name "VCCIN") (class "Default")
      (node (ref "C406") (pin "2") (pinfunction "2_2") (pintype "passive"))
      (node (ref "C407") (pin "2") (pinfunction "2_2") (pintype "passive"))
      (node (ref "C408") (pin "2") (pinfunction "2_2") (pintype "passive"))
      (node (ref "C409") (pin "2") (pinfunction "2_2") (pintype "passive"))
      (node (ref "R569") (pin "2") (pinfunction "2_2") (pintype "passive"))
      (node (ref "U18") (pin "2") (pinfunction "VIN_2") (pintype "passive"))
    )
    (net (code "34") (name "VCC_1V8") (class "Default")
      (node (ref "FB21") (pin "2") (pinfunction "2_2") (pintype "passive"))
      (node (ref "FB22") (pin "2") (pinfunction "2_2") (pintype "passive"))
    )
    (net (code "35") (name "VCC_3V3") (class "Default")
      (node (ref "FB17") (pin "2") (pinfunction "2_2") (pintype "passive"))
      (node (ref "FB18") (pin "2") (pinfunction "2_2") (pintype "passive"))
      (node (ref "R553") (pin "1") (pinfunction "1_1") (pintype "passive"))
    )
    (net (code "36") (name "VCC_3V3_EXT") (class "Default")
      (node (ref "FB19") (pin "2") (pinfunction "2_2") (pintype "passive"))
      (node (ref "FB20") (pin "2") (pinfunction "2_2") (pintype "passive"))
      (node (ref "R559") (pin "1") (pinfunction "1_1") (pintype "passive"))
    )
    (net (code "37") (name "VCC_3V3_LED") (class "Default")
      (node (ref "FB23") (pin "2") (pinfunction "2_2") (pintype "passive"))
      (node (ref "FB24") (pin "2") (pinfunction "2_2") (pintype "passive"))
      (node (ref "R570") (pin "1") (pinfunction "1_1") (pintype "passive"))
    )
    (net (code "38") (name "VCC_5V0") (class "Default")
      (node (ref "C373") (pin "2") (pinfunction "2_2") (pintype "passive"))
      (node (ref "C374") (pin "2") (pinfunction "2_2") (pintype "passive"))
      (node (ref "C375") (pin "2") (pinfunction "2_2") (pintype "passive"))
      (node (ref "C376") (pin "2") (pinfunction "2_2") (pintype "passive"))
      (node (ref "C384") (pin "2") (pinfunction "2_2") (pintype "passive"))
      (node (ref "C385") (pin "2") (pinfunction "2_2") (pintype "passive"))
      (node (ref "C386") (pin "2") (pinfunction "2_2") (pintype "passive"))
      (node (ref "C387") (pin "2") (pinfunction "2_2") (pintype "passive"))
      (node (ref "C395") (pin "2") (pinfunction "2_2") (pintype "passive"))
      (node (ref "C396") (pin "2") (pinfunction "2_2") (pintype "passive"))
      (node (ref "C397") (pin "2") (pinfunction "2_2") (pintype "passive"))
      (node (ref "C398") (pin "2") (pinfunction "2_2") (pintype "passive"))
      (node (ref "R552") (pin "2") (pinfunction "2_2") (pintype "passive"))
      (node (ref "R558") (pin "2") (pinfunction "2_2") (pintype "passive"))
      (node (ref "R564") (pin "2") (pinfunction "2_2") (pintype "passive"))
      (node (ref "U15") (pin "2") (pinfunction "VIN_2") (pintype "passive"))
      (node (ref "U16") (pin "2") (pinfunction "VIN_2") (pintype "passive"))
      (node (ref "U17") (pin "2") (pinfunction "VIN_2") (pintype "passive"))
    )
  )
)
